# BLE_--_HM-10_--_Breakout_v0_9_3brd.net
KiCad netlist of a schematic drawn in EAGLE
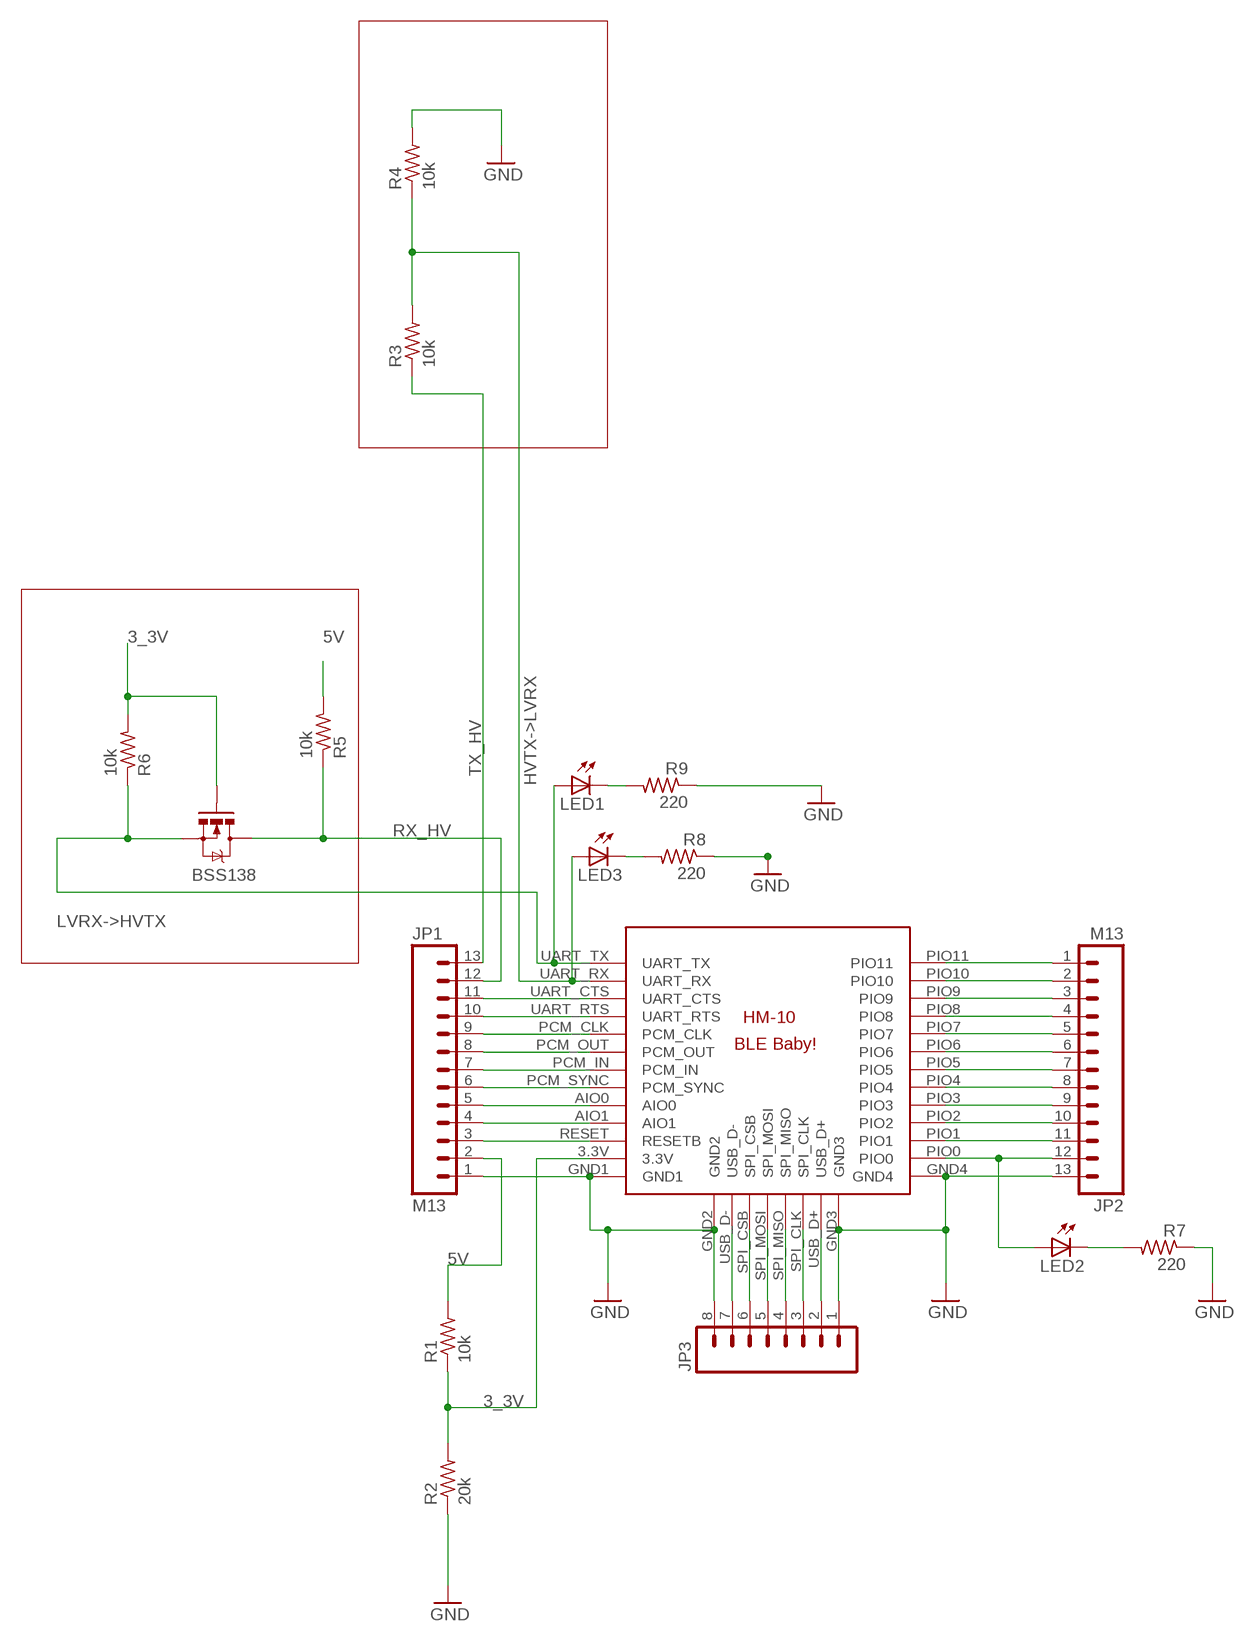
[diagram p0: schematic, sheet 1]

(export (version "E")
  (design (tool "Eeschema 10.0.6"))
  (components
    (comp (ref "BSS138")
      (value "MOSFET-NCHANNELSMD")
      (footprint "eagle-import:SOT23-3")
      (libsource (lib "eagle-import") (part "MOSFET-NCHANNELSMD"))
    )
    (comp (ref "JP1")
      (value "M13")
      (footprint "eagle-import:1X13")
      (libsource (lib "eagle-import") (part "M13"))
    )
    (comp (ref "JP2")
      (value "M13")
      (footprint "eagle-import:1X13")
      (libsource (lib "eagle-import") (part "M13"))
    )
    (comp (ref "JP3")
      (value "M081X08")
      (footprint "eagle-import:1X08")
      (libsource (lib "eagle-import") (part "M081X08"))
    )
    (comp (ref "LED1")
      (value "LED0603")
      (footprint "eagle-import:LED-0603")
      (libsource (lib "eagle-import") (part "LED0603"))
    )
    (comp (ref "LED2")
      (value "LED0603")
      (footprint "eagle-import:LED-0603")
      (libsource (lib "eagle-import") (part "LED0603"))
    )
    (comp (ref "LED3")
      (value "LED0603")
      (footprint "eagle-import:LED-0603")
      (libsource (lib "eagle-import") (part "LED0603"))
    )
    (comp (ref "R1")
      (value "10k")
      (footprint "eagle-import:M0805")
      (libsource (lib "eagle-import") (part "R-US_M0805"))
    )
    (comp (ref "R2")
      (value "20k")
      (footprint "eagle-import:M0805")
      (libsource (lib "eagle-import") (part "R-US_M0805"))
    )
    (comp (ref "R3")
      (value "10k")
      (footprint "eagle-import:M0805")
      (libsource (lib "eagle-import") (part "R-US_M0805"))
    )
    (comp (ref "R4")
      (value "10k")
      (footprint "eagle-import:M0805")
      (libsource (lib "eagle-import") (part "R-US_M0805"))
    )
    (comp (ref "R5")
      (value "10k")
      (footprint "eagle-import:M0805")
      (libsource (lib "eagle-import") (part "R-US_M0805"))
    )
    (comp (ref "R6")
      (value "10k")
      (footprint "eagle-import:M0805")
      (libsource (lib "eagle-import") (part "R-US_M0805"))
    )
    (comp (ref "R7")
      (value "220")
      (footprint "eagle-import:M0805")
      (libsource (lib "eagle-import") (part "R-US_M0805"))
    )
    (comp (ref "R8")
      (value "220")
      (footprint "eagle-import:M0805")
      (libsource (lib "eagle-import") (part "R-US_M0805"))
    )
    (comp (ref "R9")
      (value "220")
      (footprint "eagle-import:M0805")
      (libsource (lib "eagle-import") (part "R-US_M0805"))
    )
    (comp (ref "U$1")
      (value "BLE-HM-10")
      (footprint "eagle-import:BLE-HM-10")
      (libsource (lib "eagle-import") (part "BLE-HM-10"))
    )
  )
  (nets
    (net (code "1") (name "/3_3V") (class "Default")
      (node (ref "BSS138") (pin "1") (pinfunction "G_1") (pintype "passive"))
      (node (ref "R1") (pin "1") (pinfunction "1_1") (pintype "passive"))
      (node (ref "R2") (pin "2") (pinfunction "2_2") (pintype "passive"))
      (node (ref "R6") (pin "2") (pinfunction "2_2") (pintype "passive"))
      (node (ref "U$1") (pin "3.3V") (pinfunction "3.3V_3.3V") (pintype "bidirectional"))
    )
    (net (code "2") (name "/5V") (class "Default")
      (node (ref "JP1") (pin "2") (pinfunction "2_2") (pintype "passive"))
      (node (ref "R1") (pin "2") (pinfunction "2_2") (pintype "passive"))
      (node (ref "R5") (pin "2") (pinfunction "2_2") (pintype "passive"))
    )
    (net (code "3") (name "/HVTX->LVRX") (class "Default")
      (node (ref "LED3") (pin "A") (pinfunction "A_A") (pintype "passive"))
      (node (ref "R3") (pin "2") (pinfunction "2_2") (pintype "passive"))
      (node (ref "R4") (pin "1") (pinfunction "1_1") (pintype "passive"))
      (node (ref "U$1") (pin "UART_RX") (pinfunction "UART_RX_UART_RX") (pintype "bidirectional"))
    )
    (net (code "4") (name "/LVRX->HVTX") (class "Default")
      (node (ref "BSS138") (pin "2") (pinfunction "S_2") (pintype "passive"))
      (node (ref "LED1") (pin "A") (pinfunction "A_A") (pintype "passive"))
      (node (ref "R6") (pin "1") (pinfunction "1_1") (pintype "passive"))
      (node (ref "U$1") (pin "UART_TX") (pinfunction "UART_TX_UART_TX") (pintype "bidirectional"))
    )
    (net (code "5") (name "/RX_HV") (class "Default")
      (node (ref "BSS138") (pin "3") (pinfunction "D_3") (pintype "passive"))
      (node (ref "JP1") (pin "12") (pinfunction "12_12") (pintype "passive"))
      (node (ref "R5") (pin "1") (pinfunction "1_1") (pintype "passive"))
    )
    (net (code "6") (name "/TX_HV") (class "Default")
      (node (ref "JP1") (pin "13") (pinfunction "13_13") (pintype "passive"))
      (node (ref "R3") (pin "1") (pinfunction "1_1") (pintype "passive"))
    )
    (net (code "7") (name "GND") (class "Default")
      (node (ref "JP1") (pin "1") (pinfunction "1_1") (pintype "passive"))
      (node (ref "JP2") (pin "13") (pinfunction "13_13") (pintype "passive"))
      (node (ref "JP3") (pin "1") (pinfunction "1_1") (pintype "passive"))
      (node (ref "JP3") (pin "8") (pinfunction "8_8") (pintype "passive"))
      (node (ref "R2") (pin "1") (pinfunction "1_1") (pintype "passive"))
      (node (ref "R4") (pin "2") (pinfunction "2_2") (pintype "passive"))
      (node (ref "R7") (pin "1") (pinfunction "1_1") (pintype "passive"))
      (node (ref "R8") (pin "1") (pinfunction "1_1") (pintype "passive"))
      (node (ref "R9") (pin "1") (pinfunction "1_1") (pintype "passive"))
      (node (ref "U$1") (pin "GND1") (pinfunction "GND1_GND1") (pintype "bidirectional"))
      (node (ref "U$1") (pin "GND2") (pinfunction "GND2_GND2") (pintype "bidirectional"))
      (node (ref "U$1") (pin "GND3") (pinfunction "GND3_GND3") (pintype "bidirectional"))
      (node (ref "U$1") (pin "GND4") (pinfunction "GND4_GND4") (pintype "bidirectional"))
    )
    (net (code "8") (name "Net-(JP1-Pad4)") (class "Default")
      (node (ref "JP1") (pin "4") (pinfunction "4_4") (pintype "passive"))
      (node (ref "U$1") (pin "AIO1") (pinfunction "AIO1_AIO1") (pintype "bidirectional"))
    )
    (net (code "9") (name "Net-(JP1-Pad5)") (class "Default")
      (node (ref "JP1") (pin "5") (pinfunction "5_5") (pintype "passive"))
      (node (ref "U$1") (pin "AIO0") (pinfunction "AIO0_AIO0") (pintype "bidirectional"))
    )
    (net (code "10") (name "Net-(JP1-Pad6)") (class "Default")
      (node (ref "JP1") (pin "6") (pinfunction "6_6") (pintype "passive"))
      (node (ref "U$1") (pin "PCM_SYNC") (pinfunction "PCM_SYNC_PCM_SYNC") (pintype "bidirectional"))
    )
    (net (code "11") (name "Net-(JP1-Pad7)") (class "Default")
      (node (ref "JP1") (pin "7") (pinfunction "7_7") (pintype "passive"))
      (node (ref "U$1") (pin "PCM_IN") (pinfunction "PCM_IN_PCM_IN") (pintype "bidirectional"))
    )
    (net (code "12") (name "Net-(JP1-Pad8)") (class "Default")
      (node (ref "JP1") (pin "8") (pinfunction "8_8") (pintype "passive"))
      (node (ref "U$1") (pin "PCM_OUT") (pinfunction "PCM_OUT_PCM_OUT") (pintype "bidirectional"))
    )
    (net (code "13") (name "Net-(JP1-Pad9)") (class "Default")
      (node (ref "JP1") (pin "9") (pinfunction "9_9") (pintype "passive"))
      (node (ref "U$1") (pin "PCM_CLK") (pinfunction "PCM_CLK_PCM_CLK") (pintype "bidirectional"))
    )
    (net (code "14") (name "Net-(JP1-Pad10)") (class "Default")
      (node (ref "JP1") (pin "10") (pinfunction "10_10") (pintype "passive"))
      (node (ref "U$1") (pin "UART_RTS") (pinfunction "UART_RTS_UART_RTS") (pintype "bidirectional"))
    )
    (net (code "15") (name "Net-(JP1-Pad11)") (class "Default")
      (node (ref "JP1") (pin "11") (pinfunction "11_11") (pintype "passive"))
      (node (ref "U$1") (pin "UART_CTS") (pinfunction "UART_CTS_UART_CTS") (pintype "bidirectional"))
    )
    (net (code "16") (name "Net-(JP2-Pad1)") (class "Default")
      (node (ref "JP2") (pin "1") (pinfunction "1_1") (pintype "passive"))
      (node (ref "U$1") (pin "PIO11") (pinfunction "PIO11_PIO11") (pintype "bidirectional"))
    )
    (net (code "17") (name "Net-(JP2-Pad2)") (class "Default")
      (node (ref "JP2") (pin "2") (pinfunction "2_2") (pintype "passive"))
      (node (ref "U$1") (pin "PIO10") (pinfunction "PIO10_PIO10") (pintype "bidirectional"))
    )
    (net (code "18") (name "Net-(JP2-Pad3)") (class "Default")
      (node (ref "JP2") (pin "3") (pinfunction "3_3") (pintype "passive"))
      (node (ref "U$1") (pin "PIO9") (pinfunction "PIO9_PIO9") (pintype "bidirectional"))
    )
    (net (code "19") (name "Net-(JP2-Pad4)") (class "Default")
      (node (ref "JP2") (pin "4") (pinfunction "4_4") (pintype "passive"))
      (node (ref "U$1") (pin "PIO8") (pinfunction "PIO8_PIO8") (pintype "bidirectional"))
    )
    (net (code "20") (name "Net-(JP2-Pad5)") (class "Default")
      (node (ref "JP2") (pin "5") (pinfunction "5_5") (pintype "passive"))
      (node (ref "U$1") (pin "PIO7") (pinfunction "PIO7_PIO7") (pintype "bidirectional"))
    )
    (net (code "21") (name "Net-(JP2-Pad6)") (class "Default")
      (node (ref "JP2") (pin "6") (pinfunction "6_6") (pintype "passive"))
      (node (ref "U$1") (pin "PIO6") (pinfunction "PIO6_PIO6") (pintype "bidirectional"))
    )
    (net (code "22") (name "Net-(JP2-Pad7)") (class "Default")
      (node (ref "JP2") (pin "7") (pinfunction "7_7") (pintype "passive"))
      (node (ref "U$1") (pin "PIO5") (pinfunction "PIO5_PIO5") (pintype "bidirectional"))
    )
    (net (code "23") (name "Net-(JP2-Pad8)") (class "Default")
      (node (ref "JP2") (pin "8") (pinfunction "8_8") (pintype "passive"))
      (node (ref "U$1") (pin "PIO4") (pinfunction "PIO4_PIO4") (pintype "bidirectional"))
    )
    (net (code "24") (name "Net-(JP2-Pad9)") (class "Default")
      (node (ref "JP2") (pin "9") (pinfunction "9_9") (pintype "passive"))
      (node (ref "U$1") (pin "PIO3") (pinfunction "PIO3_PIO3") (pintype "bidirectional"))
    )
    (net (code "25") (name "Net-(JP2-Pad10)") (class "Default")
      (node (ref "JP2") (pin "10") (pinfunction "10_10") (pintype "passive"))
      (node (ref "U$1") (pin "PIO2") (pinfunction "PIO2_PIO2") (pintype "bidirectional"))
    )
    (net (code "26") (name "Net-(JP2-Pad11)") (class "Default")
      (node (ref "JP2") (pin "11") (pinfunction "11_11") (pintype "passive"))
      (node (ref "U$1") (pin "PIO1") (pinfunction "PIO1_PIO1") (pintype "bidirectional"))
    )
    (net (code "27") (name "Net-(JP2-Pad12)") (class "Default")
      (node (ref "JP2") (pin "12") (pinfunction "12_12") (pintype "passive"))
      (node (ref "LED2") (pin "A") (pinfunction "A_A") (pintype "passive"))
      (node (ref "U$1") (pin "PIO0") (pinfunction "PIO0_PIO0") (pintype "bidirectional"))
    )
    (net (code "28") (name "Net-(JP3-Pad2)") (class "Default")
      (node (ref "JP3") (pin "2") (pinfunction "2_2") (pintype "passive"))
      (node (ref "U$1") (pin "USB_D+") (pinfunction "USB_D+_USB_D+") (pintype "bidirectional"))
    )
    (net (code "29") (name "Net-(JP3-Pad3)") (class "Default")
      (node (ref "JP3") (pin "3") (pinfunction "3_3") (pintype "passive"))
      (node (ref "U$1") (pin "SPI_CLK") (pinfunction "SPI_CLK_SPI_CLK") (pintype "bidirectional"))
    )
    (net (code "30") (name "Net-(JP3-Pad4)") (class "Default")
      (node (ref "JP3") (pin "4") (pinfunction "4_4") (pintype "passive"))
      (node (ref "U$1") (pin "SPI_MISO") (pinfunction "SPI_MISO_SPI_MISO") (pintype "bidirectional"))
    )
    (net (code "31") (name "Net-(JP3-Pad5)") (class "Default")
      (node (ref "JP3") (pin "5") (pinfunction "5_5") (pintype "passive"))
      (node (ref "U$1") (pin "SPI_MOSI") (pinfunction "SPI_MOSI_SPI_MOSI") (pintype "bidirectional"))
    )
    (net (code "32") (name "Net-(JP3-Pad6)") (class "Default")
      (node (ref "JP3") (pin "6") (pinfunction "6_6") (pintype "passive"))
      (node (ref "U$1") (pin "SPI_CSB") (pinfunction "SPI_CSB_SPI_CSB") (pintype "bidirectional"))
    )
    (net (code "33") (name "Net-(JP3-Pad7)") (class "Default")
      (node (ref "JP3") (pin "7") (pinfunction "7_7") (pintype "passive"))
      (node (ref "U$1") (pin "USB_D-") (pinfunction "USB_D-_USB_D-") (pintype "bidirectional"))
    )
    (net (code "34") (name "Net-(LED1-PadC)") (class "Default")
      (node (ref "LED1") (pin "C") (pinfunction "C_C") (pintype "passive"))
      (node (ref "R9") (pin "2") (pinfunction "2_2") (pintype "passive"))
    )
    (net (code "35") (name "Net-(LED2-PadC)") (class "Default")
      (node (ref "LED2") (pin "C") (pinfunction "C_C") (pintype "passive"))
      (node (ref "R7") (pin "2") (pinfunction "2_2") (pintype "passive"))
    )
    (net (code "36") (name "Net-(LED3-PadC)") (class "Default")
      (node (ref "LED3") (pin "C") (pinfunction "C_C") (pintype "passive"))
      (node (ref "R8") (pin "2") (pinfunction "2_2") (pintype "passive"))
    )
    (net (code "37") (name "Net-(U$1-RESETB)") (class "Default")
      (node (ref "JP1") (pin "3") (pinfunction "3_3") (pintype "passive"))
      (node (ref "U$1") (pin "RESET") (pinfunction "RESETB_RESET") (pintype "bidirectional"))
    )
  )
)
